# CH571_Core.net
KiCad netlist of a schematic drawn in Altium Designer
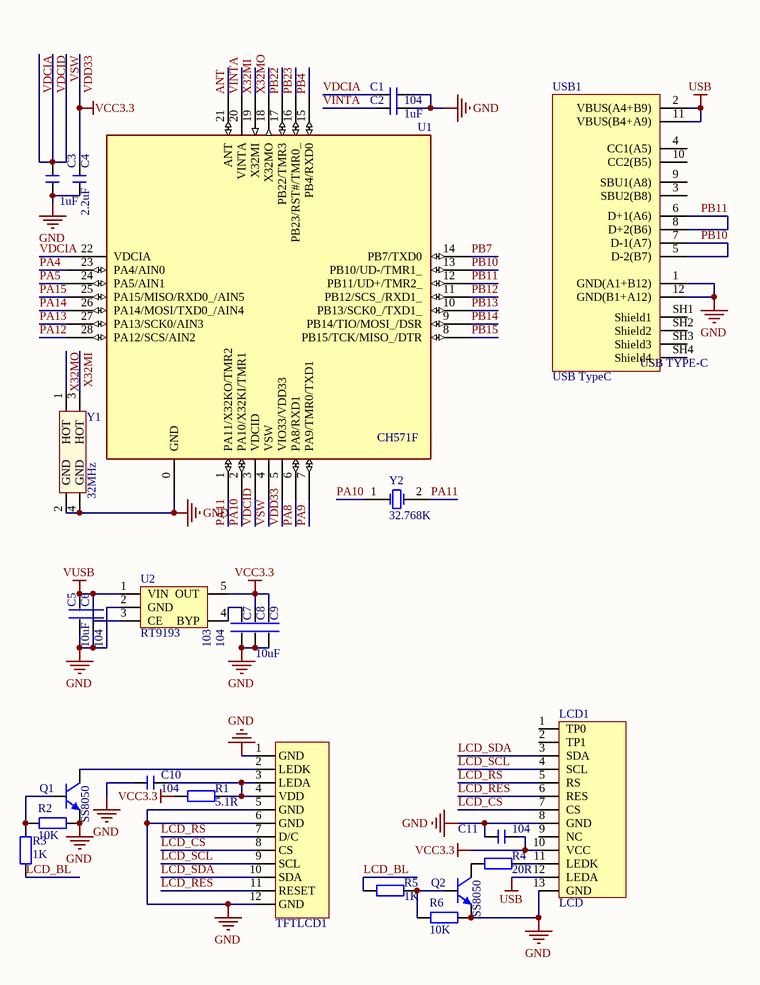
[diagram p0: CH571_Core.SchDoc]

(export (version "E")
  (design (tool "Eeschema 10.0.6"))
  (components
    (comp (ref "C1")
      (value "104")
      (footprint "C 0603_L")
      (description "无极性贴片电容")
      (libsource (lib "LovelessingSch") (part "C"))
    )
    (comp (ref "C2")
      (value "1uF")
      (footprint "C 0603_L")
      (description "无极性贴片电容")
      (libsource (lib "LovelessingSch") (part "C"))
    )
    (comp (ref "C3")
      (value "1uF")
      (footprint "C 0603_L")
      (description "无极性贴片电容")
      (libsource (lib "LovelessingSch") (part "C"))
    )
    (comp (ref "C4")
      (value "2.2uF")
      (footprint "C 0603_L")
      (description "无极性贴片电容")
      (libsource (lib "LovelessingSch") (part "C"))
    )
    (comp (ref "C5")
      (value "10uF")
      (footprint "C 0603_L")
      (libsource (lib "WarShip V3 STM32103封装库") (part "C"))
    )
    (comp (ref "C6")
      (value "104")
      (footprint "C 0603_L")
      (libsource (lib "WarShip V3 STM32103封装库") (part "C"))
    )
    (comp (ref "C7")
      (value "103")
      (footprint "C 0603_L")
      (libsource (lib "WarShip V3 STM32103封装库") (part "C"))
    )
    (comp (ref "C8")
      (value "104")
      (footprint "C 0603_L")
      (libsource (lib "WarShip V3 STM32103封装库") (part "C"))
    )
    (comp (ref "C9")
      (value "10uF")
      (footprint "C 0603_L")
      (libsource (lib "WarShip V3 STM32103封装库") (part "C"))
    )
    (comp (ref "C10")
      (value "104")
      (footprint "C 0603_L")
      (description "无极性电容")
      (fields (field (name "版权归属") "正点原子"))
      (libsource (lib "正点原子封装库V1.0") (part "C"))
    )
    (comp (ref "C11")
      (value "104")
      (footprint "C 0603_L")
      (description "无极性电容")
      (fields (field (name "版权归属") "正点原子"))
      (libsource (lib "正点原子封装库V1.0") (part "C"))
    )
    (comp (ref "LCD1")
      (value "LCD")
      (footprint "0.96LCD")
      (description "0.96 LCD 80*160")
      (fields (field (name "版权归属") "正点原子"))
      (libsource (lib "正点原子封装库V1.0") (part "LCD 0.96"))
    )
    (comp (ref "Q1")
      (value "SS8050")
      (footprint "SOT23-3L")
      (description "高频放大-NPN型")
      (fields (field (name "版权归属") "正点原子"))
      (libsource (lib "正点原子封装库V1.0") (part "8050-SMD"))
    )
    (comp (ref "Q2")
      (value "SS8050")
      (footprint "SOT23-3N")
      (description "高频放大-NPN型")
      (fields (field (name "版权归属") "正点原子"))
      (libsource (lib "正点原子封装库V1.0") (part "8050-SMD"))
    )
    (comp (ref "R1")
      (value "5.1R")
      (footprint "R 0805_L")
      (description "贴片电阻")
      (libsource (lib "LovelessingSch") (part "R"))
    )
    (comp (ref "R2")
      (value "10K")
      (footprint "R 0603_L")
      (description "贴片电阻")
      (libsource (lib "LovelessingSch") (part "R"))
    )
    (comp (ref "R3")
      (value "1K")
      (footprint "R 0603_L")
      (description "贴片电阻")
      (libsource (lib "LovelessingSch") (part "R"))
    )
    (comp (ref "R4")
      (value "20R")
      (footprint "R 0603_L")
      (description "贴片电阻")
      (libsource (lib "LovelessingSch") (part "R"))
    )
    (comp (ref "R5")
      (value "1K")
      (footprint "R 0603_L")
      (description "贴片电阻")
      (libsource (lib "LovelessingSch") (part "R"))
    )
    (comp (ref "R6")
      (value "10K")
      (footprint "R 0603_L")
      (description "贴片电阻")
      (libsource (lib "LovelessingSch") (part "R"))
    )
    (comp (ref "TFTLCD1")
      (value "TFTLCD-N133-2424THBIG01")
      (footprint "TFT-N133-2424THBIG01")
      (description "TFTLCD,240*240,SPI")
      (libsource (lib "ATK-MD0130 V2.0") (part "TFTLCD-N133-2424THBIG01"))
    )
    (comp (ref "U1")
      (value "CH571F")
      (footprint "QFN28_4X4")
      (description "RISC-V MCU with BLE/USB/ADC/SPI/2*UART")
      (libsource (lib "LovelessingSch") (part "CH571F"))
    )
    (comp (ref "U2")
      (value "RT9193")
      (footprint "SOT23-5L")
      (description "3.3V 500mA LDO")
      (libsource (lib "STM32H743核心板封装库") (part "CAT6219-330TD"))
    )
    (comp (ref "USB1")
      (value "USB TypeC")
      (footprint "USB2.0 Type-C")
      (description "12P TypeC 母座")
      (fields (field (name "版权归属") "正点原子"))
      (libsource (lib "正点原子封装库V1.0") (part "USB 2.0 Type C"))
    )
    (comp (ref "Y1")
      (value "32MHz")
      (footprint "OSC 3225-4P")
      (description "晶振25MHz")
      (fields (field (name "PUBLISHER") "Altium Limited"))
      (libsource (lib "LovelessingSch") (part "Y-3225-4P"))
    )
    (comp (ref "Y2")
      (value "32.768K")
      (footprint "OSC 3215-2P")
      (description "晶振32.768K")
      (fields (field (name "PUBLISHER") "Altium Limited"))
      (libsource (lib "LovelessingSch") (part "Y-3215-2P"))
    )
  )
  (nets
    (net (code "1") (name "/ANT") (class "Default")
      (node (ref "U1") (pin "21") (pinfunction "ANT_21") (pintype "bidirectional"))
    )
    (net (code "2") (name "/LCD_BL") (class "Default")
      (node (ref "R3") (pin "1") (pinfunction "1_1") (pintype "passive"))
      (node (ref "R5") (pin "1") (pinfunction "1_1") (pintype "passive"))
    )
    (net (code "3") (name "/LCD_CS") (class "Default")
      (node (ref "LCD1") (pin "7") (pinfunction "CS_7") (pintype "passive"))
      (node (ref "TFTLCD1") (pin "8") (pinfunction "CS_8") (pintype "passive"))
    )
    (net (code "4") (name "/LCD_RES") (class "Default")
      (node (ref "LCD1") (pin "6") (pinfunction "RES_6") (pintype "passive"))
      (node (ref "TFTLCD1") (pin "11") (pinfunction "RESET_11") (pintype "passive"))
    )
    (net (code "5") (name "/LCD_RS") (class "Default")
      (node (ref "LCD1") (pin "5") (pinfunction "RS_5") (pintype "passive"))
      (node (ref "TFTLCD1") (pin "7") (pinfunction "D/C_7") (pintype "passive"))
    )
    (net (code "6") (name "/LCD_SCL") (class "Default")
      (node (ref "LCD1") (pin "4") (pinfunction "SCL_4") (pintype "passive"))
      (node (ref "TFTLCD1") (pin "9") (pinfunction "SCL_9") (pintype "passive"))
    )
    (net (code "7") (name "/LCD_SDA") (class "Default")
      (node (ref "LCD1") (pin "3") (pinfunction "SDA_3") (pintype "passive"))
      (node (ref "TFTLCD1") (pin "10") (pinfunction "SDA_10") (pintype "passive"))
    )
    (net (code "8") (name "/PA4") (class "Default")
      (node (ref "U1") (pin "23") (pinfunction "PA4/AIN0_23") (pintype "bidirectional"))
    )
    (net (code "9") (name "/PA5") (class "Default")
      (node (ref "U1") (pin "24") (pinfunction "PA5/AIN1_24") (pintype "bidirectional"))
    )
    (net (code "10") (name "/PA8") (class "Default")
      (node (ref "U1") (pin "6") (pinfunction "PA8/RXD1_6") (pintype "bidirectional"))
    )
    (net (code "11") (name "/PA9") (class "Default")
      (node (ref "U1") (pin "7") (pinfunction "PA9/TMR0/TXD1_7") (pintype "bidirectional"))
    )
    (net (code "12") (name "/PA10") (class "Default")
      (node (ref "U1") (pin "2") (pinfunction "PA10/X32KI/TMR1_2") (pintype "bidirectional"))
      (node (ref "Y2") (pin "1") (pinfunction "OSC1_1") (pintype "passive"))
    )
    (net (code "13") (name "/PA11") (class "Default")
      (node (ref "U1") (pin "1") (pinfunction "PA11/X32KO/TMR2_1") (pintype "bidirectional"))
      (node (ref "Y2") (pin "2") (pinfunction "OSC2_2") (pintype "passive"))
    )
    (net (code "14") (name "/PA12") (class "Default")
      (node (ref "U1") (pin "28") (pinfunction "PA12/SCS/AIN2_28") (pintype "bidirectional"))
    )
    (net (code "15") (name "/PA13") (class "Default")
      (node (ref "U1") (pin "27") (pinfunction "PA13/SCK0/AIN3_27") (pintype "bidirectional"))
    )
    (net (code "16") (name "/PA14") (class "Default")
      (node (ref "U1") (pin "26") (pinfunction "PA14/MOSI/TXD0_/AIN4_26") (pintype "bidirectional"))
    )
    (net (code "17") (name "/PA15") (class "Default")
      (node (ref "U1") (pin "25") (pinfunction "PA15/MISO/RXD0_/AIN5_25") (pintype "bidirectional"))
    )
    (net (code "18") (name "/PB4") (class "Default")
      (node (ref "U1") (pin "15") (pinfunction "PB4/RXD0_15") (pintype "bidirectional"))
    )
    (net (code "19") (name "/PB7") (class "Default")
      (node (ref "U1") (pin "14") (pinfunction "PB7/TXD0_14") (pintype "bidirectional"))
    )
    (net (code "20") (name "/PB10") (class "Default")
      (node (ref "U1") (pin "13") (pinfunction "PB10/UD-/TMR1__13") (pintype "bidirectional"))
      (node (ref "USB1") (pin "5") (pinfunction "D-2(B7)_5") (pintype "passive"))
      (node (ref "USB1") (pin "7") (pinfunction "D-1(A7)_7") (pintype "passive"))
    )
    (net (code "21") (name "/PB11") (class "Default")
      (node (ref "U1") (pin "12") (pinfunction "PB11/UD+/TMR2__12") (pintype "bidirectional"))
      (node (ref "USB1") (pin "6") (pinfunction "D+1(A6)_6") (pintype "passive"))
      (node (ref "USB1") (pin "8") (pinfunction "D+2(B6)_8") (pintype "passive"))
    )
    (net (code "22") (name "/PB12") (class "Default")
      (node (ref "U1") (pin "11") (pinfunction "PB12/SCS_/RXD1__11") (pintype "bidirectional"))
    )
    (net (code "23") (name "/PB13") (class "Default")
      (node (ref "U1") (pin "10") (pinfunction "PB13/SCK0_/TXD1__10") (pintype "bidirectional"))
    )
    (net (code "24") (name "/PB14") (class "Default")
      (node (ref "U1") (pin "9") (pinfunction "PB14/TIO/MOSI_/DSR_9") (pintype "bidirectional"))
    )
    (net (code "25") (name "/PB15") (class "Default")
      (node (ref "U1") (pin "8") (pinfunction "PB15/TCK/MISO_/DTR_8") (pintype "bidirectional"))
    )
    (net (code "26") (name "/PB22") (class "Default")
      (node (ref "U1") (pin "17") (pinfunction "PB22/TMR3_17") (pintype "bidirectional"))
    )
    (net (code "27") (name "/PB23") (class "Default")
      (node (ref "U1") (pin "16") (pinfunction "PB23/RST#/TMR0__16") (pintype "bidirectional"))
    )
    (net (code "28") (name "/VDCIA") (class "Default")
      (node (ref "C1") (pin "1") (pinfunction "1_1") (pintype "passive"))
      (node (ref "C3") (pin "1") (pinfunction "1_1") (pintype "passive"))
      (node (ref "U1") (pin "22") (pinfunction "VDCIA_22") (pintype "power_in"))
      (node (ref "U1") (pin "3") (pinfunction "VDCID_3") (pintype "power_in"))
      (node (ref "U1") (pin "4") (pinfunction "VSW_4") (pintype "power_in"))
    )
    (net (code "29") (name "/VINTA") (class "Default")
      (node (ref "C2") (pin "1") (pinfunction "1_1") (pintype "passive"))
      (node (ref "U1") (pin "20") (pinfunction "VINTA_20") (pintype "power_in"))
    )
    (net (code "30") (name "/X32MI") (class "Default")
      (node (ref "U1") (pin "19") (pinfunction "X32MI_19") (pintype "input"))
      (node (ref "Y1") (pin "3") (pinfunction "HOT_3") (pintype "passive"))
    )
    (net (code "31") (name "/X32MO") (class "Default")
      (node (ref "U1") (pin "18") (pinfunction "X32MO_18") (pintype "output"))
      (node (ref "Y1") (pin "1") (pinfunction "HOT_1") (pintype "passive"))
    )
    (net (code "32") (name "GND") (class "Default")
      (node (ref "C1") (pin "2") (pinfunction "2_2") (pintype "passive"))
      (node (ref "C10") (pin "2") (pinfunction "2_2") (pintype "passive"))
      (node (ref "C11") (pin "2") (pinfunction "2_2") (pintype "passive"))
      (node (ref "C2") (pin "2") (pinfunction "2_2") (pintype "passive"))
      (node (ref "C3") (pin "2") (pinfunction "2_2") (pintype "passive"))
      (node (ref "C4") (pin "2") (pinfunction "2_2") (pintype "passive"))
      (node (ref "C5") (pin "1") (pintype "passive"))
      (node (ref "C6") (pin "1") (pintype "passive"))
      (node (ref "C7") (pin "1") (pintype "passive"))
      (node (ref "C8") (pin "1") (pintype "passive"))
      (node (ref "C9") (pin "1") (pintype "passive"))
      (node (ref "LCD1") (pin "13") (pinfunction "GND_13") (pintype "passive"))
      (node (ref "LCD1") (pin "8") (pinfunction "GND_8") (pintype "passive"))
      (node (ref "Q1") (pin "2") (pinfunction "E_2") (pintype "passive"))
      (node (ref "Q2") (pin "2") (pinfunction "E_2") (pintype "passive"))
      (node (ref "R2") (pin "2") (pinfunction "2_2") (pintype "passive"))
      (node (ref "R6") (pin "2") (pinfunction "2_2") (pintype "passive"))
      (node (ref "TFTLCD1") (pin "1") (pinfunction "GND_1") (pintype "passive"))
      (node (ref "TFTLCD1") (pin "12") (pinfunction "GND_12") (pintype "passive"))
      (node (ref "TFTLCD1") (pin "5") (pinfunction "GND_5") (pintype "passive"))
      (node (ref "TFTLCD1") (pin "6") (pinfunction "GND_6") (pintype "passive"))
      (node (ref "U1") (pin "0") (pinfunction "GND_0") (pintype "power_in"))
      (node (ref "U2") (pin "2") (pinfunction "GND_2") (pintype "passive"))
      (node (ref "USB1") (pin "1") (pinfunction "GND(A1+B12)_1") (pintype "passive"))
      (node (ref "USB1") (pin "12") (pinfunction "GND(B1+A12)_12") (pintype "passive"))
      (node (ref "Y1") (pin "2") (pinfunction "GND_2") (pintype "passive"))
      (node (ref "Y1") (pin "4") (pinfunction "GND_4") (pintype "passive"))
    )
    (net (code "33") (name "Net-(LCD1-LEDK)") (class "Default")
      (node (ref "LCD1") (pin "11") (pinfunction "LEDK_11") (pintype "passive"))
      (node (ref "R4") (pin "2") (pinfunction "2_2") (pintype "passive"))
    )
    (net (code "34") (name "Net-(Q1-B)") (class "Default")
      (node (ref "Q1") (pin "1") (pinfunction "B_1") (pintype "passive"))
      (node (ref "R2") (pin "1") (pinfunction "1_1") (pintype "passive"))
      (node (ref "R3") (pin "2") (pinfunction "2_2") (pintype "passive"))
    )
    (net (code "35") (name "Net-(Q1-C)") (class "Default")
      (node (ref "Q1") (pin "3") (pinfunction "C_3") (pintype "passive"))
      (node (ref "TFTLCD1") (pin "2") (pinfunction "LEDK_2") (pintype "passive"))
    )
    (net (code "36") (name "Net-(Q2-B)") (class "Default")
      (node (ref "Q2") (pin "1") (pinfunction "B_1") (pintype "passive"))
      (node (ref "R5") (pin "2") (pinfunction "2_2") (pintype "passive"))
      (node (ref "R6") (pin "1") (pinfunction "1_1") (pintype "passive"))
    )
    (net (code "37") (name "Net-(Q2-C)") (class "Default")
      (node (ref "Q2") (pin "3") (pinfunction "C_3") (pintype "passive"))
      (node (ref "R4") (pin "1") (pinfunction "1_1") (pintype "passive"))
    )
    (net (code "38") (name "Net-(TFTLCD1-LEDA)") (class "Default")
      (node (ref "C10") (pin "1") (pinfunction "1_1") (pintype "passive"))
      (node (ref "R1") (pin "2") (pinfunction "2_2") (pintype "passive"))
      (node (ref "TFTLCD1") (pin "3") (pinfunction "LEDA_3") (pintype "passive"))
      (node (ref "TFTLCD1") (pin "4") (pinfunction "VDD_4") (pintype "passive"))
    )
    (net (code "39") (name "Net-(U2-BYP)") (class "Default")
      (node (ref "C7") (pin "2") (pintype "passive"))
      (node (ref "U2") (pin "4") (pinfunction "BYP_4") (pintype "passive"))
    )
    (net (code "40") (name "USB") (class "Default")
      (node (ref "LCD1") (pin "12") (pinfunction "LEDA_12") (pintype "passive"))
      (node (ref "USB1") (pin "11") (pinfunction "VBUS(B4+A9)_11") (pintype "passive"))
      (node (ref "USB1") (pin "2") (pinfunction "VBUS(A4+B9)_2") (pintype "passive"))
    )
    (net (code "41") (name "VCC3.3") (class "Default")
      (node (ref "C11") (pin "1") (pinfunction "1_1") (pintype "passive"))
      (node (ref "C4") (pin "1") (pinfunction "1_1") (pintype "passive"))
      (node (ref "C8") (pin "2") (pintype "passive"))
      (node (ref "C9") (pin "2") (pintype "passive"))
      (node (ref "LCD1") (pin "10") (pinfunction "VCC_10") (pintype "passive"))
      (node (ref "R1") (pin "1") (pinfunction "1_1") (pintype "passive"))
      (node (ref "U1") (pin "5") (pinfunction "VIO33/VDD33_5") (pintype "power_in"))
      (node (ref "U2") (pin "5") (pinfunction "OUT_5") (pintype "passive"))
    )
    (net (code "42") (name "VUSB") (class "Default")
      (node (ref "C5") (pin "2") (pintype "passive"))
      (node (ref "C6") (pin "2") (pintype "passive"))
      (node (ref "U2") (pin "1") (pinfunction "VIN_1") (pintype "passive"))
      (node (ref "U2") (pin "3") (pinfunction "CE_3") (pintype "passive"))
    )
    (net (code "43") (name "unconnected-(LCD1-NC-Pad9)") (class "Default")
      (node (ref "LCD1") (pin "9") (pinfunction "NC_9") (pintype "passive"))
    )
    (net (code "44") (name "unconnected-(LCD1-TP0-Pad1)") (class "Default")
      (node (ref "LCD1") (pin "1") (pinfunction "TP0_1") (pintype "passive"))
    )
    (net (code "45") (name "unconnected-(LCD1-TP1-Pad2)") (class "Default")
      (node (ref "LCD1") (pin "2") (pinfunction "TP1_2") (pintype "passive"))
    )
    (net (code "46") (name "unconnected-(USB1-CC1(A5)-Pad4)") (class "Default")
      (node (ref "USB1") (pin "4") (pinfunction "CC1(A5)_4") (pintype "passive"))
    )
    (net (code "47") (name "unconnected-(USB1-CC2(B5)-Pad10)") (class "Default")
      (node (ref "USB1") (pin "10") (pinfunction "CC2(B5)_10") (pintype "passive"))
    )
    (net (code "48") (name "unconnected-(USB1-SBU1(A8)-Pad9)") (class "Default")
      (node (ref "USB1") (pin "9") (pinfunction "SBU1(A8)_9") (pintype "passive"))
    )
    (net (code "49") (name "unconnected-(USB1-SBU2(B8)-Pad3)") (class "Default")
      (node (ref "USB1") (pin "3") (pinfunction "SBU2(B8)_3") (pintype "passive"))
    )
    (net (code "50") (name "unconnected-(USB1-Shield1-PadSH1)") (class "Default")
      (node (ref "USB1") (pin "SH1") (pinfunction "Shield1_SH1") (pintype "passive"))
    )
    (net (code "51") (name "unconnected-(USB1-Shield2-PadSH2)") (class "Default")
      (node (ref "USB1") (pin "SH2") (pinfunction "Shield2_SH2") (pintype "passive"))
    )
    (net (code "52") (name "unconnected-(USB1-Shield3-PadSH3)") (class "Default")
      (node (ref "USB1") (pin "SH3") (pinfunction "Shield3_SH3") (pintype "passive"))
    )
    (net (code "53") (name "unconnected-(USB1-Shield4-PadSH4)") (class "Default")
      (node (ref "USB1") (pin "SH4") (pinfunction "Shield4_SH4") (pintype "passive"))
    )
  )
)
